# 02-MCU.net
KiCad netlist of a schematic drawn in Altium Designer
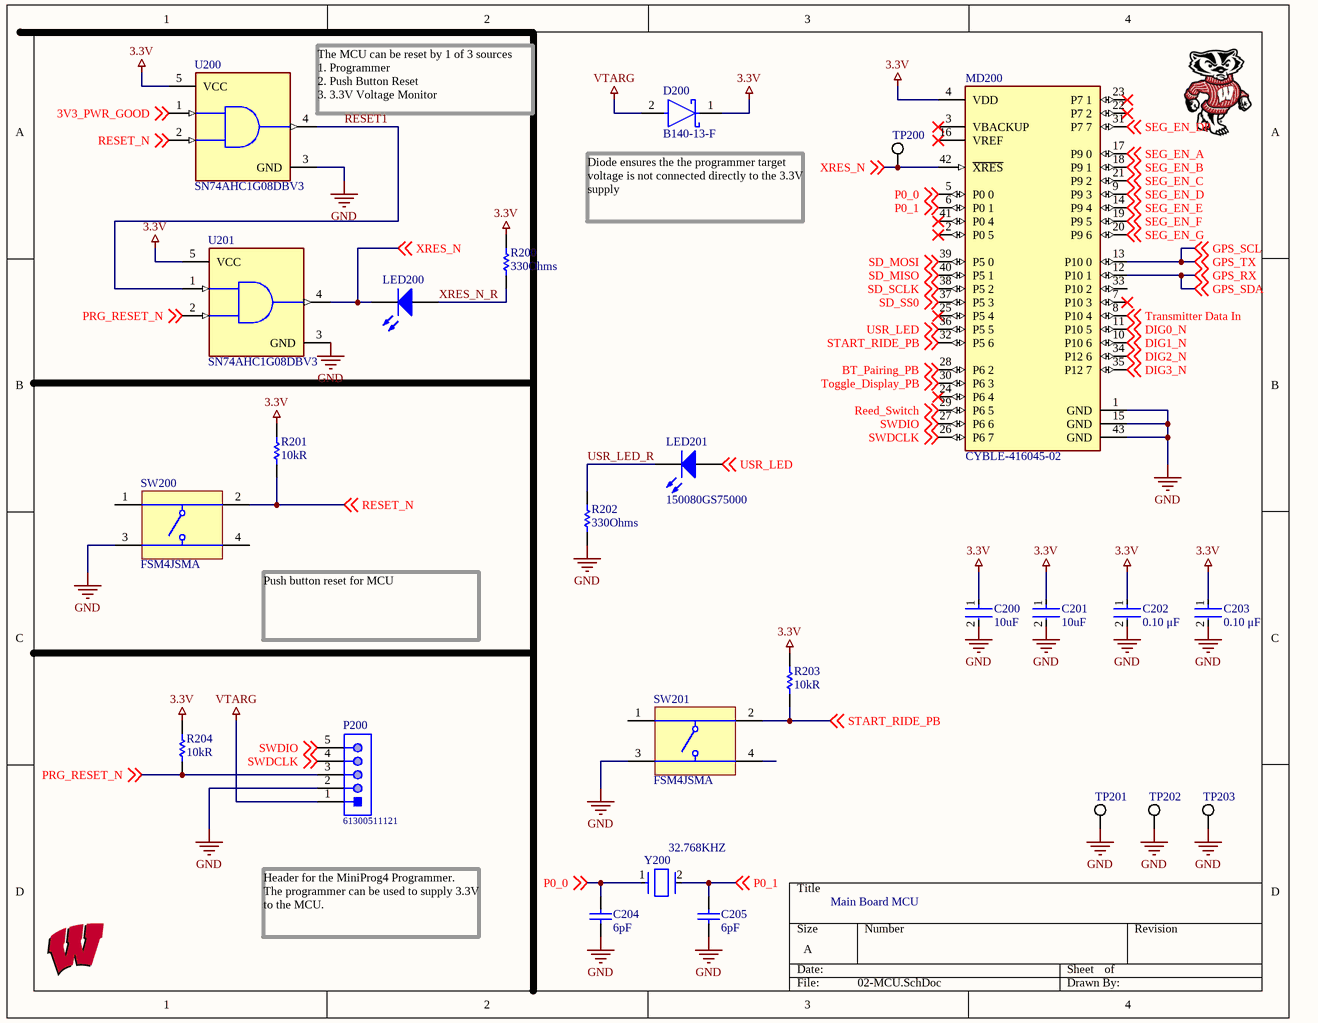
[diagram p0: 02-MCU.SchDoc]

(export (version "E")
  (design (tool "Eeschema 10.0.6"))
  (components
    (comp (ref "C200")
      (value "10uF")
      (footprint "FP-C0805C-DG-MFG")
      (description "CAP CER 10UF 10V X5R 0805")
      (fields (field (name "TOLERANCE") "10%") (field (name "MANUFACTURER PART NUMBER") "C0805C106K8PACTU"))
      (libsource (lib "Altium Content Vault") (part "11868f565c42a9108669ba33697ecf6"))
    )
    (comp (ref "C201")
      (value "10uF")
      (footprint "FP-C0805C-DG-MFG")
      (description "CAP CER 10UF 10V X5R 0805")
      (fields (field (name "TOLERANCE") "10%") (field (name "MANUFACTURER PART NUMBER") "C0805C106K8PACTU"))
      (libsource (lib "Altium Content Vault") (part "11868f565c42a9108669ba33697ecf6"))
    )
    (comp (ref "C202")
      (value "0.10 μF")
      (footprint "FP-C0805C-DN-MFG")
      (description "CAP CER 0.1UF 50V X7R 0805")
      (fields
        (field (name "MANUFACTURER PART NUMBER") "C0805C104K5RACTU")
        (field (name "MANUFACTURER") "KEMET")
      )
      (libsource (lib "Altium Content Vault") (part "b4654b650e69147ec39a6b967a45e02"))
    )
    (comp (ref "C203")
      (value "0.10 μF")
      (footprint "FP-C0805C-DN-MFG")
      (description "CAP CER 0.1UF 50V X7R 0805")
      (fields
        (field (name "MANUFACTURER PART NUMBER") "C0805C104K5RACTU")
        (field (name "MANUFACTURER") "KEMET")
      )
      (libsource (lib "Altium Content Vault") (part "b4654b650e69147ec39a6b967a45e02"))
    )
    (comp (ref "C204")
      (value "08055A6R0CAT2A")
      (footprint "CAPC2013X94X50LL20T25")
      (fields (field (name "MANUFACTURER") "AVX Interconnect / Elco") (field (name "CAPACITANCE") "6pF"))
      (libsource (lib "Altium Content Vault") (part "CAP"))
    )
    (comp (ref "C205")
      (value "08055A6R0CAT2A")
      (footprint "CAPC2013X94X50LL20T25")
      (fields (field (name "MANUFACTURER") "AVX Interconnect / Elco") (field (name "CAPACITANCE") "6pF"))
      (libsource (lib "Altium Content Vault") (part "CAP"))
    )
    (comp (ref "D200")
      (value "B140-13-F")
      (footprint "FP-SMA-MFG")
      (description "DIODE SCHOTTKY 40V 1A SMA")
      (libsource (lib "Altium Content Vault") (part "1d6ec82d83fb6aee721767c19dac4b9"))
    )
    (comp (ref "LED200")
      (value "150080RS75000")
      (footprint "0805_A")
      (description "SMD mono-color Chip LED, WL-SMCW, Red")
      (fields (field (name "MANUFACTURER") "Wuerth Elektronik"))
      (libsource (lib "Altium Content Vault") (part "WE-LED_K1A2-2"))
    )
    (comp (ref "LED201")
      (value "150080GS75000")
      (footprint "0805_A")
      (description "SMD mono-color Chip LED, WL-SMCW, Green")
      (fields (field (name "MANUFACTURER") "Wuerth Elektronik"))
      (libsource (lib "Altium Content Vault") (part "WE-LED_K1A2-2"))
    )
    (comp (ref "MD200")
      (value "CYBLE-416045-02")
      (footprint "FP-CYBLE-416045-02-MFG")
      (description "RF TXRX MOD BLUETOOTH TRACE ANT")
      (fields
        (field (name "OCTOPART") "https://octopart.com/cyble-416045-02-cypress+semiconductor-96386825")
        (field (name "MANUFACTURER") "Cypress Semiconductor")
      )
      (libsource (lib "Altium Content Vault") (part "10a29a4e77099fbb6f911efb04878b1"))
    )
    (comp (ref "P200")
      (value "61300511121")
      (footprint "61300511121")
      (description "THT Vertical Pin Header WR-PHD, Pitch 2.54 mm, Single Row, 5 pins")
      (fields (field (name "MANUFACTURER") "Wurth Elektronik") (field (name "PUBLISHER") "WurthElektronik"))
      (libsource (lib "Altium Content Vault") (part "WE-CN-1P-M-R5"))
    )
    (comp (ref "R200")
      (value "RC0805FR-07330RL")
      (footprint "RESC2013X60X35LL10T20")
      (description "Chip Resistor, 330 Ohm, +/- 1%, 125 mW, -55 to 155 degC, 0805 (2012 Metric), RoHS, Tape and Reel")
      (fields
        (field (name "MANUFACTURER") "Yageo")
        (field (name "TOLERANCE") "1%")
        (field (name "RESISTANCE") "330Ohms")
      )
      (libsource (lib "Altium Content Vault") (part "RES-2"))
    )
    (comp (ref "R201")
      (value "RC0805FR-0710KL")
      (footprint "RESC2013X60X35NL10T20")
      (description "Chip Resistor, 10 KOhm, +/- 1%, 0.125 W, -55 to 155 degC, 0805 (2012 Metric), RoHS, Tape and Reel")
      (fields
        (field (name "MANUFACTURER") "Yageo")
        (field (name "RESISTANCE") "10kR")
        (field (name "TOLERANCE") "1%")
      )
      (libsource (lib "Altium Content Vault") (part "RES-2"))
    )
    (comp (ref "R202")
      (value "RC0805FR-07330RL")
      (footprint "RESC2013X60X35LL10T20")
      (description "Chip Resistor, 330 Ohm, +/- 1%, 125 mW, -55 to 155 degC, 0805 (2012 Metric), RoHS, Tape and Reel")
      (fields
        (field (name "MANUFACTURER") "Yageo")
        (field (name "TOLERANCE") "1%")
        (field (name "RESISTANCE") "330Ohms")
      )
      (libsource (lib "Altium Content Vault") (part "RES-2"))
    )
    (comp (ref "R203")
      (value "RC0805FR-0710KL")
      (footprint "RESC2013X60X35NL10T20")
      (description "Chip Resistor, 10 KOhm, +/- 1%, 0.125 W, -55 to 155 degC, 0805 (2012 Metric), RoHS, Tape and Reel")
      (fields
        (field (name "MANUFACTURER") "Yageo")
        (field (name "RESISTANCE") "10kR")
        (field (name "TOLERANCE") "1%")
      )
      (libsource (lib "Altium Content Vault") (part "RES-2"))
    )
    (comp (ref "R204")
      (value "RC0805FR-0710KL")
      (footprint "RESC2013X60X35NL10T20")
      (description "Chip Resistor, 10 KOhm, +/- 1%, 0.125 W, -55 to 155 degC, 0805 (2012 Metric), RoHS, Tape and Reel")
      (fields
        (field (name "MANUFACTURER") "Yageo")
        (field (name "RESISTANCE") "10kR")
        (field (name "TOLERANCE") "1%")
      )
      (libsource (lib "Altium Content Vault") (part "RES-2"))
    )
    (comp (ref "SW200")
      (value "FSM4JSMA")
      (footprint "TECO-FSM4JSMA_V")
      (description "Swicth, SPST, 24 V, -35 to 85 degC, 4-Pin SMD, RoHS, Tape and Reel")
      (fields (field (name "MANUFACTURER") "TE Connectivity"))
      (libsource (lib "Altium Content Vault") (part "SW-SPST-4_A"))
    )
    (comp (ref "SW201")
      (value "FSM4JSMA")
      (footprint "TECO-FSM4JSMA_V")
      (description "Swicth, SPST, 24 V, -35 to 85 degC, 4-Pin SMD, RoHS, Tape and Reel")
      (fields (field (name "MANUFACTURER") "TE Connectivity"))
      (libsource (lib "Altium Content Vault") (part "SW-SPST-4_A"))
    )
    (comp (ref "TP200")
      (value "5019")
      (footprint "KSTN-5019_V")
      (description "Test Point, 1 Position SMD, RoHS, Tape and Reel")
      (libsource (lib "Altium Content Vault") (part "TESTPOINT_WHITE"))
    )
    (comp (ref "TP201")
      (value "5019")
      (footprint "KSTN-5019_V")
      (description "Test Point, 1 Position SMD, RoHS, Tape and Reel")
      (libsource (lib "Altium Content Vault") (part "TESTPOINT_WHITE"))
    )
    (comp (ref "TP202")
      (value "5019")
      (footprint "KSTN-5019_V")
      (description "Test Point, 1 Position SMD, RoHS, Tape and Reel")
      (libsource (lib "Altium Content Vault") (part "TESTPOINT_WHITE"))
    )
    (comp (ref "TP203")
      (value "5019")
      (footprint "KSTN-5019_V")
      (description "Test Point, 1 Position SMD, RoHS, Tape and Reel")
      (libsource (lib "Altium Content Vault") (part "TESTPOINT_WHITE"))
    )
    (comp (ref "U200")
      (value "SN74AHC1G08DBV3")
      (footprint "FP-DBV0005A-IPC_C")
      (description "IC GATE AND 1CH 2-INP SOT23-5")
      (libsource (lib "Altium Content Vault") (part "675e79b427d6219a5295bf943425e1c"))
    )
    (comp (ref "U201")
      (value "SN74AHC1G08DBV3")
      (footprint "FP-DBV0005A-IPC_C")
      (description "IC GATE AND 1CH 2-INP SOT23-5")
      (libsource (lib "Altium Content Vault") (part "675e79b427d6219a5295bf943425e1c"))
    )
    (comp (ref "Y200")
      (value "32.768KHZ")
      (footprint "FP-ABS07-120-MFG")
      (description "CRYSTAL 32.7680KHZ 6PF SMD")
      (fields (field (name "TOLERANCE") "20ppm"))
      (libsource (lib "Altium Content Vault") (part "c23a69dc6c9e2f18f2079038eb95dd1"))
    )
  )
  (nets
    (net (code "1") (name "/RESET1") (class "Default")
      (node (ref "U200") (pin "4") (pinfunction "Y_4") (pintype "output"))
      (node (ref "U201") (pin "1") (pinfunction "A_1") (pintype "input"))
    )
    (net (code "2") (name "/USR_LED_R") (class "Default")
      (node (ref "LED201") (pin "1") (pinfunction "K_1") (pintype "passive"))
      (node (ref "R202") (pin "2") (pinfunction "2_2") (pintype "passive"))
    )
    (net (code "3") (name "/XRES_N_R") (class "Default")
      (node (ref "LED200") (pin "2") (pinfunction "A_2") (pintype "passive"))
      (node (ref "R200") (pin "1") (pinfunction "1_1") (pintype "passive"))
    )
    (net (code "4") (name "3.3V") (class "Default")
      (node (ref "C200") (pin "1") (pinfunction "1_1") (pintype "passive"))
      (node (ref "C201") (pin "1") (pinfunction "1_1") (pintype "passive"))
      (node (ref "C202") (pin "1") (pinfunction "1_1") (pintype "passive"))
      (node (ref "C203") (pin "1") (pinfunction "1_1") (pintype "passive"))
      (node (ref "D200") (pin "1") (pinfunction "C_1") (pintype "passive"))
      (node (ref "MD200") (pin "4") (pinfunction "VDD_4") (pintype "power_in"))
      (node (ref "R200") (pin "2") (pinfunction "2_2") (pintype "passive"))
      (node (ref "R201") (pin "2") (pinfunction "2_2") (pintype "passive"))
      (node (ref "R203") (pin "2") (pinfunction "2_2") (pintype "passive"))
      (node (ref "R204") (pin "2") (pinfunction "2_2") (pintype "passive"))
      (node (ref "U200") (pin "5") (pinfunction "VCC_5") (pintype "power_in"))
      (node (ref "U201") (pin "5") (pinfunction "VCC_5") (pintype "power_in"))
    )
    (net (code "5") (name "3V3_PWR_GOOD") (class "Default")
      (node (ref "U200") (pin "1") (pinfunction "A_1") (pintype "input"))
    )
    (net (code "6") (name "BT_Pairing_PB") (class "Default")
      (node (ref "MD200") (pin "28") (pinfunction "P6_2_28") (pintype "bidirectional"))
    )
    (net (code "7") (name "DIG0_N") (class "Default")
      (node (ref "MD200") (pin "11") (pinfunction "P10_5_11") (pintype "bidirectional"))
    )
    (net (code "8") (name "DIG1_N") (class "Default")
      (node (ref "MD200") (pin "10") (pinfunction "P10_6_10") (pintype "bidirectional"))
    )
    (net (code "9") (name "DIG2_N") (class "Default")
      (node (ref "MD200") (pin "34") (pinfunction "P12_6_34") (pintype "bidirectional"))
    )
    (net (code "10") (name "DIG3_N") (class "Default")
      (node (ref "MD200") (pin "35") (pinfunction "P12_7_35") (pintype "bidirectional"))
    )
    (net (code "11") (name "GND") (class "Default")
      (node (ref "C200") (pin "2") (pinfunction "2_2") (pintype "passive"))
      (node (ref "C201") (pin "2") (pinfunction "2_2") (pintype "passive"))
      (node (ref "C202") (pin "2") (pinfunction "2_2") (pintype "passive"))
      (node (ref "C203") (pin "2") (pinfunction "2_2") (pintype "passive"))
      (node (ref "C204") (pin "1") (pinfunction "1_1") (pintype "passive"))
      (node (ref "C205") (pin "1") (pinfunction "1_1") (pintype "passive"))
      (node (ref "MD200") (pin "1") (pinfunction "GND_1") (pintype "power_in"))
      (node (ref "MD200") (pin "15") (pinfunction "GND_15") (pintype "power_in"))
      (node (ref "MD200") (pin "43") (pinfunction "GND_43") (pintype "power_in"))
      (node (ref "P200") (pin "2") (pinfunction "2_2") (pintype "passive"))
      (node (ref "R202") (pin "1") (pinfunction "1_1") (pintype "passive"))
      (node (ref "SW200") (pin "3") (pinfunction "3_3") (pintype "passive"))
      (node (ref "SW201") (pin "3") (pinfunction "3_3") (pintype "passive"))
      (node (ref "TP201") (pin "1") (pinfunction "1_1") (pintype "passive"))
      (node (ref "TP202") (pin "1") (pinfunction "1_1") (pintype "passive"))
      (node (ref "TP203") (pin "1") (pinfunction "1_1") (pintype "passive"))
      (node (ref "U200") (pin "3") (pinfunction "GND_3") (pintype "power_in"))
      (node (ref "U201") (pin "3") (pinfunction "GND_3") (pintype "power_in"))
    )
    (net (code "12") (name "GPS_RX") (class "Default")
      (node (ref "MD200") (pin "12") (pinfunction "P10_1_12") (pintype "bidirectional"))
    )
    (net (code "13") (name "GPS_SCL") (class "Default")
      (node (ref "MD200") (pin "13") (pinfunction "P10_0_13") (pintype "bidirectional"))
    )
    (net (code "14") (name "P0_0") (class "Default")
      (node (ref "C204") (pin "2") (pinfunction "2_2") (pintype "passive"))
      (node (ref "MD200") (pin "5") (pinfunction "P0_0_5") (pintype "bidirectional"))
      (node (ref "Y200") (pin "1") (pinfunction "1_1") (pintype "passive"))
    )
    (net (code "15") (name "P0_1") (class "Default")
      (node (ref "C205") (pin "2") (pinfunction "2_2") (pintype "passive"))
      (node (ref "MD200") (pin "6") (pinfunction "P0_1_6") (pintype "bidirectional"))
      (node (ref "Y200") (pin "2") (pinfunction "2_2") (pintype "passive"))
    )
    (net (code "16") (name "PRG_RESET_N") (class "Default")
      (node (ref "P200") (pin "3") (pinfunction "3_3") (pintype "passive"))
      (node (ref "R204") (pin "1") (pinfunction "1_1") (pintype "passive"))
      (node (ref "U201") (pin "2") (pinfunction "B_2") (pintype "input"))
    )
    (net (code "17") (name "RESET_N") (class "Default")
      (node (ref "R201") (pin "1") (pinfunction "1_1") (pintype "passive"))
      (node (ref "SW200") (pin "2") (pinfunction "2_2") (pintype "passive"))
      (node (ref "U200") (pin "2") (pinfunction "B_2") (pintype "input"))
    )
    (net (code "18") (name "Reed_Switch") (class "Default")
      (node (ref "MD200") (pin "29") (pinfunction "P6_5_29") (pintype "bidirectional"))
    )
    (net (code "19") (name "SD_MISO") (class "Default")
      (node (ref "MD200") (pin "40") (pinfunction "P5_1_40") (pintype "bidirectional"))
    )
    (net (code "20") (name "SD_MOSI") (class "Default")
      (node (ref "MD200") (pin "39") (pinfunction "P5_0_39") (pintype "bidirectional"))
    )
    (net (code "21") (name "SD_SCLK") (class "Default")
      (node (ref "MD200") (pin "38") (pinfunction "P5_2_38") (pintype "bidirectional"))
    )
    (net (code "22") (name "SD_SS0") (class "Default")
      (node (ref "MD200") (pin "37") (pinfunction "P5_3_37") (pintype "bidirectional"))
    )
    (net (code "23") (name "SEG_EN_A") (class "Default")
      (node (ref "MD200") (pin "17") (pinfunction "P9_0_17") (pintype "bidirectional"))
    )
    (net (code "24") (name "SEG_EN_B") (class "Default")
      (node (ref "MD200") (pin "18") (pinfunction "P9_1_18") (pintype "bidirectional"))
    )
    (net (code "25") (name "SEG_EN_C") (class "Default")
      (node (ref "MD200") (pin "21") (pinfunction "P9_2_21") (pintype "bidirectional"))
    )
    (net (code "26") (name "SEG_EN_D") (class "Default")
      (node (ref "MD200") (pin "9") (pinfunction "P9_3_9") (pintype "bidirectional"))
    )
    (net (code "27") (name "SEG_EN_DP") (class "Default")
      (node (ref "MD200") (pin "31") (pinfunction "P7_7_31") (pintype "bidirectional"))
    )
    (net (code "28") (name "SEG_EN_E") (class "Default")
      (node (ref "MD200") (pin "14") (pinfunction "P9_4_14") (pintype "bidirectional"))
    )
    (net (code "29") (name "SEG_EN_F") (class "Default")
      (node (ref "MD200") (pin "19") (pinfunction "P9_5_19") (pintype "bidirectional"))
    )
    (net (code "30") (name "SEG_EN_G") (class "Default")
      (node (ref "MD200") (pin "20") (pinfunction "P9_6_20") (pintype "bidirectional"))
    )
    (net (code "31") (name "START_RIDE_PB") (class "Default")
      (node (ref "MD200") (pin "32") (pinfunction "P5_6_32") (pintype "bidirectional"))
      (node (ref "R203") (pin "1") (pinfunction "1_1") (pintype "passive"))
      (node (ref "SW201") (pin "2") (pinfunction "2_2") (pintype "passive"))
    )
    (net (code "32") (name "SWDCLK") (class "Default")
      (node (ref "MD200") (pin "26") (pinfunction "P6_7_26") (pintype "bidirectional"))
      (node (ref "P200") (pin "4") (pinfunction "4_4") (pintype "passive"))
    )
    (net (code "33") (name "SWDIO") (class "Default")
      (node (ref "MD200") (pin "27") (pinfunction "P6_6_27") (pintype "bidirectional"))
      (node (ref "P200") (pin "5") (pinfunction "5_5") (pintype "passive"))
    )
    (net (code "34") (name "Toggle_Display_PB") (class "Default")
      (node (ref "MD200") (pin "30") (pinfunction "P6_3_30") (pintype "bidirectional"))
    )
    (net (code "35") (name "Transmitter Data In") (class "Default")
      (node (ref "MD200") (pin "8") (pinfunction "P10_4_8") (pintype "bidirectional"))
    )
    (net (code "36") (name "USR_LED") (class "Default")
      (node (ref "LED201") (pin "2") (pinfunction "A_2") (pintype "passive"))
      (node (ref "MD200") (pin "36") (pinfunction "P5_5_36") (pintype "bidirectional"))
    )
    (net (code "37") (name "VTARG") (class "Default")
      (node (ref "D200") (pin "2") (pinfunction "A_2") (pintype "passive"))
      (node (ref "P200") (pin "1") (pinfunction "1_1") (pintype "passive"))
    )
    (net (code "38") (name "XRES_N") (class "Default")
      (node (ref "LED200") (pin "1") (pinfunction "K_1") (pintype "passive"))
      (node (ref "MD200") (pin "42") (pinfunction "~{XRES}_42") (pintype "input"))
      (node (ref "TP200") (pin "1") (pinfunction "1_1") (pintype "passive"))
      (node (ref "U201") (pin "4") (pinfunction "Y_4") (pintype "output"))
    )
    (net (code "39") (name "unconnected-(MD200-P0_4-Pad41)") (class "Default")
      (node (ref "MD200") (pin "41") (pinfunction "P0_4_41") (pintype "bidirectional+no_connect"))
    )
    (net (code "40") (name "unconnected-(MD200-P0_5-Pad2)") (class "Default")
      (node (ref "MD200") (pin "2") (pinfunction "P0_5_2") (pintype "bidirectional+no_connect"))
    )
    (net (code "41") (name "unconnected-(MD200-P5_4-Pad25)") (class "Default")
      (node (ref "MD200") (pin "25") (pinfunction "P5_4_25") (pintype "bidirectional+no_connect"))
    )
    (net (code "42") (name "unconnected-(MD200-P6_4-Pad24)") (class "Default")
      (node (ref "MD200") (pin "24") (pinfunction "P6_4_24") (pintype "bidirectional+no_connect"))
    )
    (net (code "43") (name "unconnected-(MD200-P7_1-Pad23)") (class "Default")
      (node (ref "MD200") (pin "23") (pinfunction "P7_1_23") (pintype "bidirectional+no_connect"))
    )
    (net (code "44") (name "unconnected-(MD200-P7_2-Pad22)") (class "Default")
      (node (ref "MD200") (pin "22") (pinfunction "P7_2_22") (pintype "bidirectional+no_connect"))
    )
    (net (code "45") (name "unconnected-(MD200-P10_2-Pad33)") (class "Default")
      (node (ref "MD200") (pin "33") (pinfunction "P10_2_33") (pintype "bidirectional"))
    )
    (net (code "46") (name "unconnected-(MD200-P10_3-Pad7)") (class "Default")
      (node (ref "MD200") (pin "7") (pinfunction "P10_3_7") (pintype "bidirectional+no_connect"))
    )
    (net (code "47") (name "unconnected-(MD200-VBACKUP-Pad3)") (class "Default")
      (node (ref "MD200") (pin "3") (pinfunction "VBACKUP_3") (pintype "power_in+no_connect"))
    )
    (net (code "48") (name "unconnected-(MD200-VREF-Pad16)") (class "Default")
      (node (ref "MD200") (pin "16") (pinfunction "VREF_16") (pintype "power_in+no_connect"))
    )
    (net (code "49") (name "unconnected-(SW200-Pad1)") (class "Default")
      (node (ref "SW200") (pin "1") (pinfunction "1_1") (pintype "passive"))
    )
    (net (code "50") (name "unconnected-(SW200-Pad4)") (class "Default")
      (node (ref "SW200") (pin "4") (pinfunction "4_4") (pintype "passive"))
    )
    (net (code "51") (name "unconnected-(SW201-Pad1)") (class "Default")
      (node (ref "SW201") (pin "1") (pinfunction "1_1") (pintype "passive"))
    )
    (net (code "52") (name "unconnected-(SW201-Pad4)") (class "Default")
      (node (ref "SW201") (pin "4") (pinfunction "4_4") (pintype "passive"))
    )
  )
)
